# 2-MIN-SYSTEM.net
KiCad netlist of a schematic drawn in Altium Designer
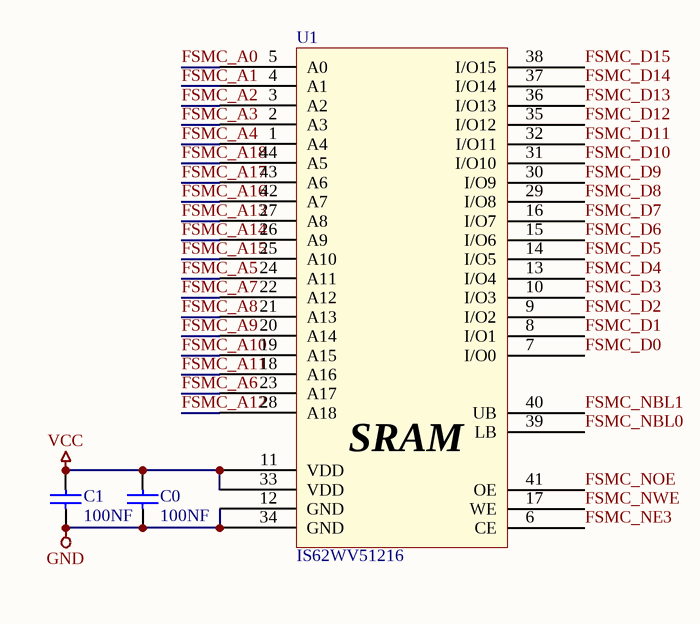
[diagram p0: 2-MIN-SYSTEM.SchDoc]

(export (version "E")
  (design (tool "Eeschema 10.0.6"))
  (components
    (comp (ref "C0")
      (value "100NF")
      (footprint "CC1608-0603")
      (description "电容")
      (fields (field (name "PUBLISHER") "Altium Limited"))
      (libsource (lib "tianxiaohua_Schlib") (part "Cap Chip 0603"))
    )
    (comp (ref "C1")
      (value "100NF")
      (footprint "CC1608-0603")
      (description "电容")
      (fields (field (name "PUBLISHER") "Altium Limited"))
      (libsource (lib "tianxiaohua_Schlib") (part "Cap Chip 0603"))
    )
    (comp (ref "U1")
      (value "IS62WV51216")
      (footprint "TSOP44_M")
      (description "SRAM")
      (libsource (lib "tianxiaohua_Schlib") (part "IS62WV51216"))
    )
  )
  (nets
    (net (code "1") (name "/FSMC_A0") (class "Default")
      (node (ref "U1") (pin "5") (pinfunction "A0_5") (pintype "passive"))
    )
    (net (code "2") (name "/FSMC_A1") (class "Default")
      (node (ref "U1") (pin "4") (pinfunction "A1_4") (pintype "passive"))
    )
    (net (code "3") (name "/FSMC_A2") (class "Default")
      (node (ref "U1") (pin "3") (pinfunction "A2_3") (pintype "passive"))
    )
    (net (code "4") (name "/FSMC_A3") (class "Default")
      (node (ref "U1") (pin "2") (pinfunction "A3_2") (pintype "passive"))
    )
    (net (code "5") (name "/FSMC_A4") (class "Default")
      (node (ref "U1") (pin "1") (pinfunction "A4_1") (pintype "passive"))
    )
    (net (code "6") (name "/FSMC_A5") (class "Default")
      (node (ref "U1") (pin "24") (pinfunction "A11_24") (pintype "passive"))
    )
    (net (code "7") (name "/FSMC_A6") (class "Default")
      (node (ref "U1") (pin "23") (pinfunction "A17_23") (pintype "passive"))
    )
    (net (code "8") (name "/FSMC_A7") (class "Default")
      (node (ref "U1") (pin "22") (pinfunction "A12_22") (pintype "passive"))
    )
    (net (code "9") (name "/FSMC_A8") (class "Default")
      (node (ref "U1") (pin "21") (pinfunction "A13_21") (pintype "passive"))
    )
    (net (code "10") (name "/FSMC_A9") (class "Default")
      (node (ref "U1") (pin "20") (pinfunction "A14_20") (pintype "passive"))
    )
    (net (code "11") (name "/FSMC_A10") (class "Default")
      (node (ref "U1") (pin "19") (pinfunction "A15_19") (pintype "passive"))
    )
    (net (code "12") (name "/FSMC_A11") (class "Default")
      (node (ref "U1") (pin "18") (pinfunction "A16_18") (pintype "passive"))
    )
    (net (code "13") (name "/FSMC_A12") (class "Default")
      (node (ref "U1") (pin "28") (pinfunction "A18_28") (pintype "passive"))
    )
    (net (code "14") (name "/FSMC_A13") (class "Default")
      (node (ref "U1") (pin "27") (pinfunction "A8_27") (pintype "passive"))
    )
    (net (code "15") (name "/FSMC_A14") (class "Default")
      (node (ref "U1") (pin "26") (pinfunction "A9_26") (pintype "passive"))
    )
    (net (code "16") (name "/FSMC_A15") (class "Default")
      (node (ref "U1") (pin "25") (pinfunction "A10_25") (pintype "passive"))
    )
    (net (code "17") (name "/FSMC_A16") (class "Default")
      (node (ref "U1") (pin "42") (pinfunction "A7_42") (pintype "passive"))
    )
    (net (code "18") (name "/FSMC_A17") (class "Default")
      (node (ref "U1") (pin "43") (pinfunction "A6_43") (pintype "passive"))
    )
    (net (code "19") (name "/FSMC_A18") (class "Default")
      (node (ref "U1") (pin "44") (pinfunction "A5_44") (pintype "passive"))
    )
    (net (code "20") (name "/FSMC_D0") (class "Default")
      (node (ref "U1") (pin "7") (pinfunction "I/O0_7") (pintype "passive"))
    )
    (net (code "21") (name "/FSMC_D1") (class "Default")
      (node (ref "U1") (pin "8") (pinfunction "I/O1_8") (pintype "passive"))
    )
    (net (code "22") (name "/FSMC_D2") (class "Default")
      (node (ref "U1") (pin "9") (pinfunction "I/O2_9") (pintype "passive"))
    )
    (net (code "23") (name "/FSMC_D3") (class "Default")
      (node (ref "U1") (pin "10") (pinfunction "I/O3_10") (pintype "passive"))
    )
    (net (code "24") (name "/FSMC_D4") (class "Default")
      (node (ref "U1") (pin "13") (pinfunction "I/O4_13") (pintype "passive"))
    )
    (net (code "25") (name "/FSMC_D5") (class "Default")
      (node (ref "U1") (pin "14") (pinfunction "I/O5_14") (pintype "passive"))
    )
    (net (code "26") (name "/FSMC_D6") (class "Default")
      (node (ref "U1") (pin "15") (pinfunction "I/O6_15") (pintype "passive"))
    )
    (net (code "27") (name "/FSMC_D7") (class "Default")
      (node (ref "U1") (pin "16") (pinfunction "I/O7_16") (pintype "passive"))
    )
    (net (code "28") (name "/FSMC_D8") (class "Default")
      (node (ref "U1") (pin "29") (pinfunction "I/O8_29") (pintype "passive"))
    )
    (net (code "29") (name "/FSMC_D9") (class "Default")
      (node (ref "U1") (pin "30") (pinfunction "I/O9_30") (pintype "passive"))
    )
    (net (code "30") (name "/FSMC_D10") (class "Default")
      (node (ref "U1") (pin "31") (pinfunction "I/O10_31") (pintype "passive"))
    )
    (net (code "31") (name "/FSMC_D11") (class "Default")
      (node (ref "U1") (pin "32") (pinfunction "I/O11_32") (pintype "passive"))
    )
    (net (code "32") (name "/FSMC_D12") (class "Default")
      (node (ref "U1") (pin "35") (pinfunction "I/O12_35") (pintype "passive"))
    )
    (net (code "33") (name "/FSMC_D13") (class "Default")
      (node (ref "U1") (pin "36") (pinfunction "I/O13_36") (pintype "passive"))
    )
    (net (code "34") (name "/FSMC_D14") (class "Default")
      (node (ref "U1") (pin "37") (pinfunction "I/O14_37") (pintype "passive"))
    )
    (net (code "35") (name "/FSMC_D15") (class "Default")
      (node (ref "U1") (pin "38") (pinfunction "I/O15_38") (pintype "passive"))
    )
    (net (code "36") (name "/FSMC_NBL0") (class "Default")
      (node (ref "U1") (pin "39") (pinfunction "LB_39") (pintype "passive"))
    )
    (net (code "37") (name "/FSMC_NBL1") (class "Default")
      (node (ref "U1") (pin "40") (pinfunction "UB_40") (pintype "passive"))
    )
    (net (code "38") (name "/FSMC_NE3") (class "Default")
      (node (ref "U1") (pin "6") (pinfunction "CE_6") (pintype "passive"))
    )
    (net (code "39") (name "/FSMC_NOE") (class "Default")
      (node (ref "U1") (pin "41") (pinfunction "OE_41") (pintype "passive"))
    )
    (net (code "40") (name "/FSMC_NWE") (class "Default")
      (node (ref "U1") (pin "17") (pinfunction "WE_17") (pintype "passive"))
    )
    (net (code "41") (name "GND") (class "Default")
      (node (ref "C0") (pin "1") (pinfunction "1_1") (pintype "passive"))
      (node (ref "C1") (pin "1") (pinfunction "1_1") (pintype "passive"))
      (node (ref "U1") (pin "12") (pinfunction "GND_12") (pintype "passive"))
      (node (ref "U1") (pin "34") (pinfunction "GND_34") (pintype "passive"))
    )
    (net (code "42") (name "VCC") (class "Default")
      (node (ref "C0") (pin "2") (pinfunction "2_2") (pintype "passive"))
      (node (ref "C1") (pin "2") (pinfunction "2_2") (pintype "passive"))
      (node (ref "U1") (pin "11") (pinfunction "VDD_11") (pintype "passive"))
      (node (ref "U1") (pin "33") (pinfunction "VDD_33") (pintype "passive"))
    )
  )
)
